# Sheet_1.net
KiCad netlist of a schematic drawn in EasyEDA
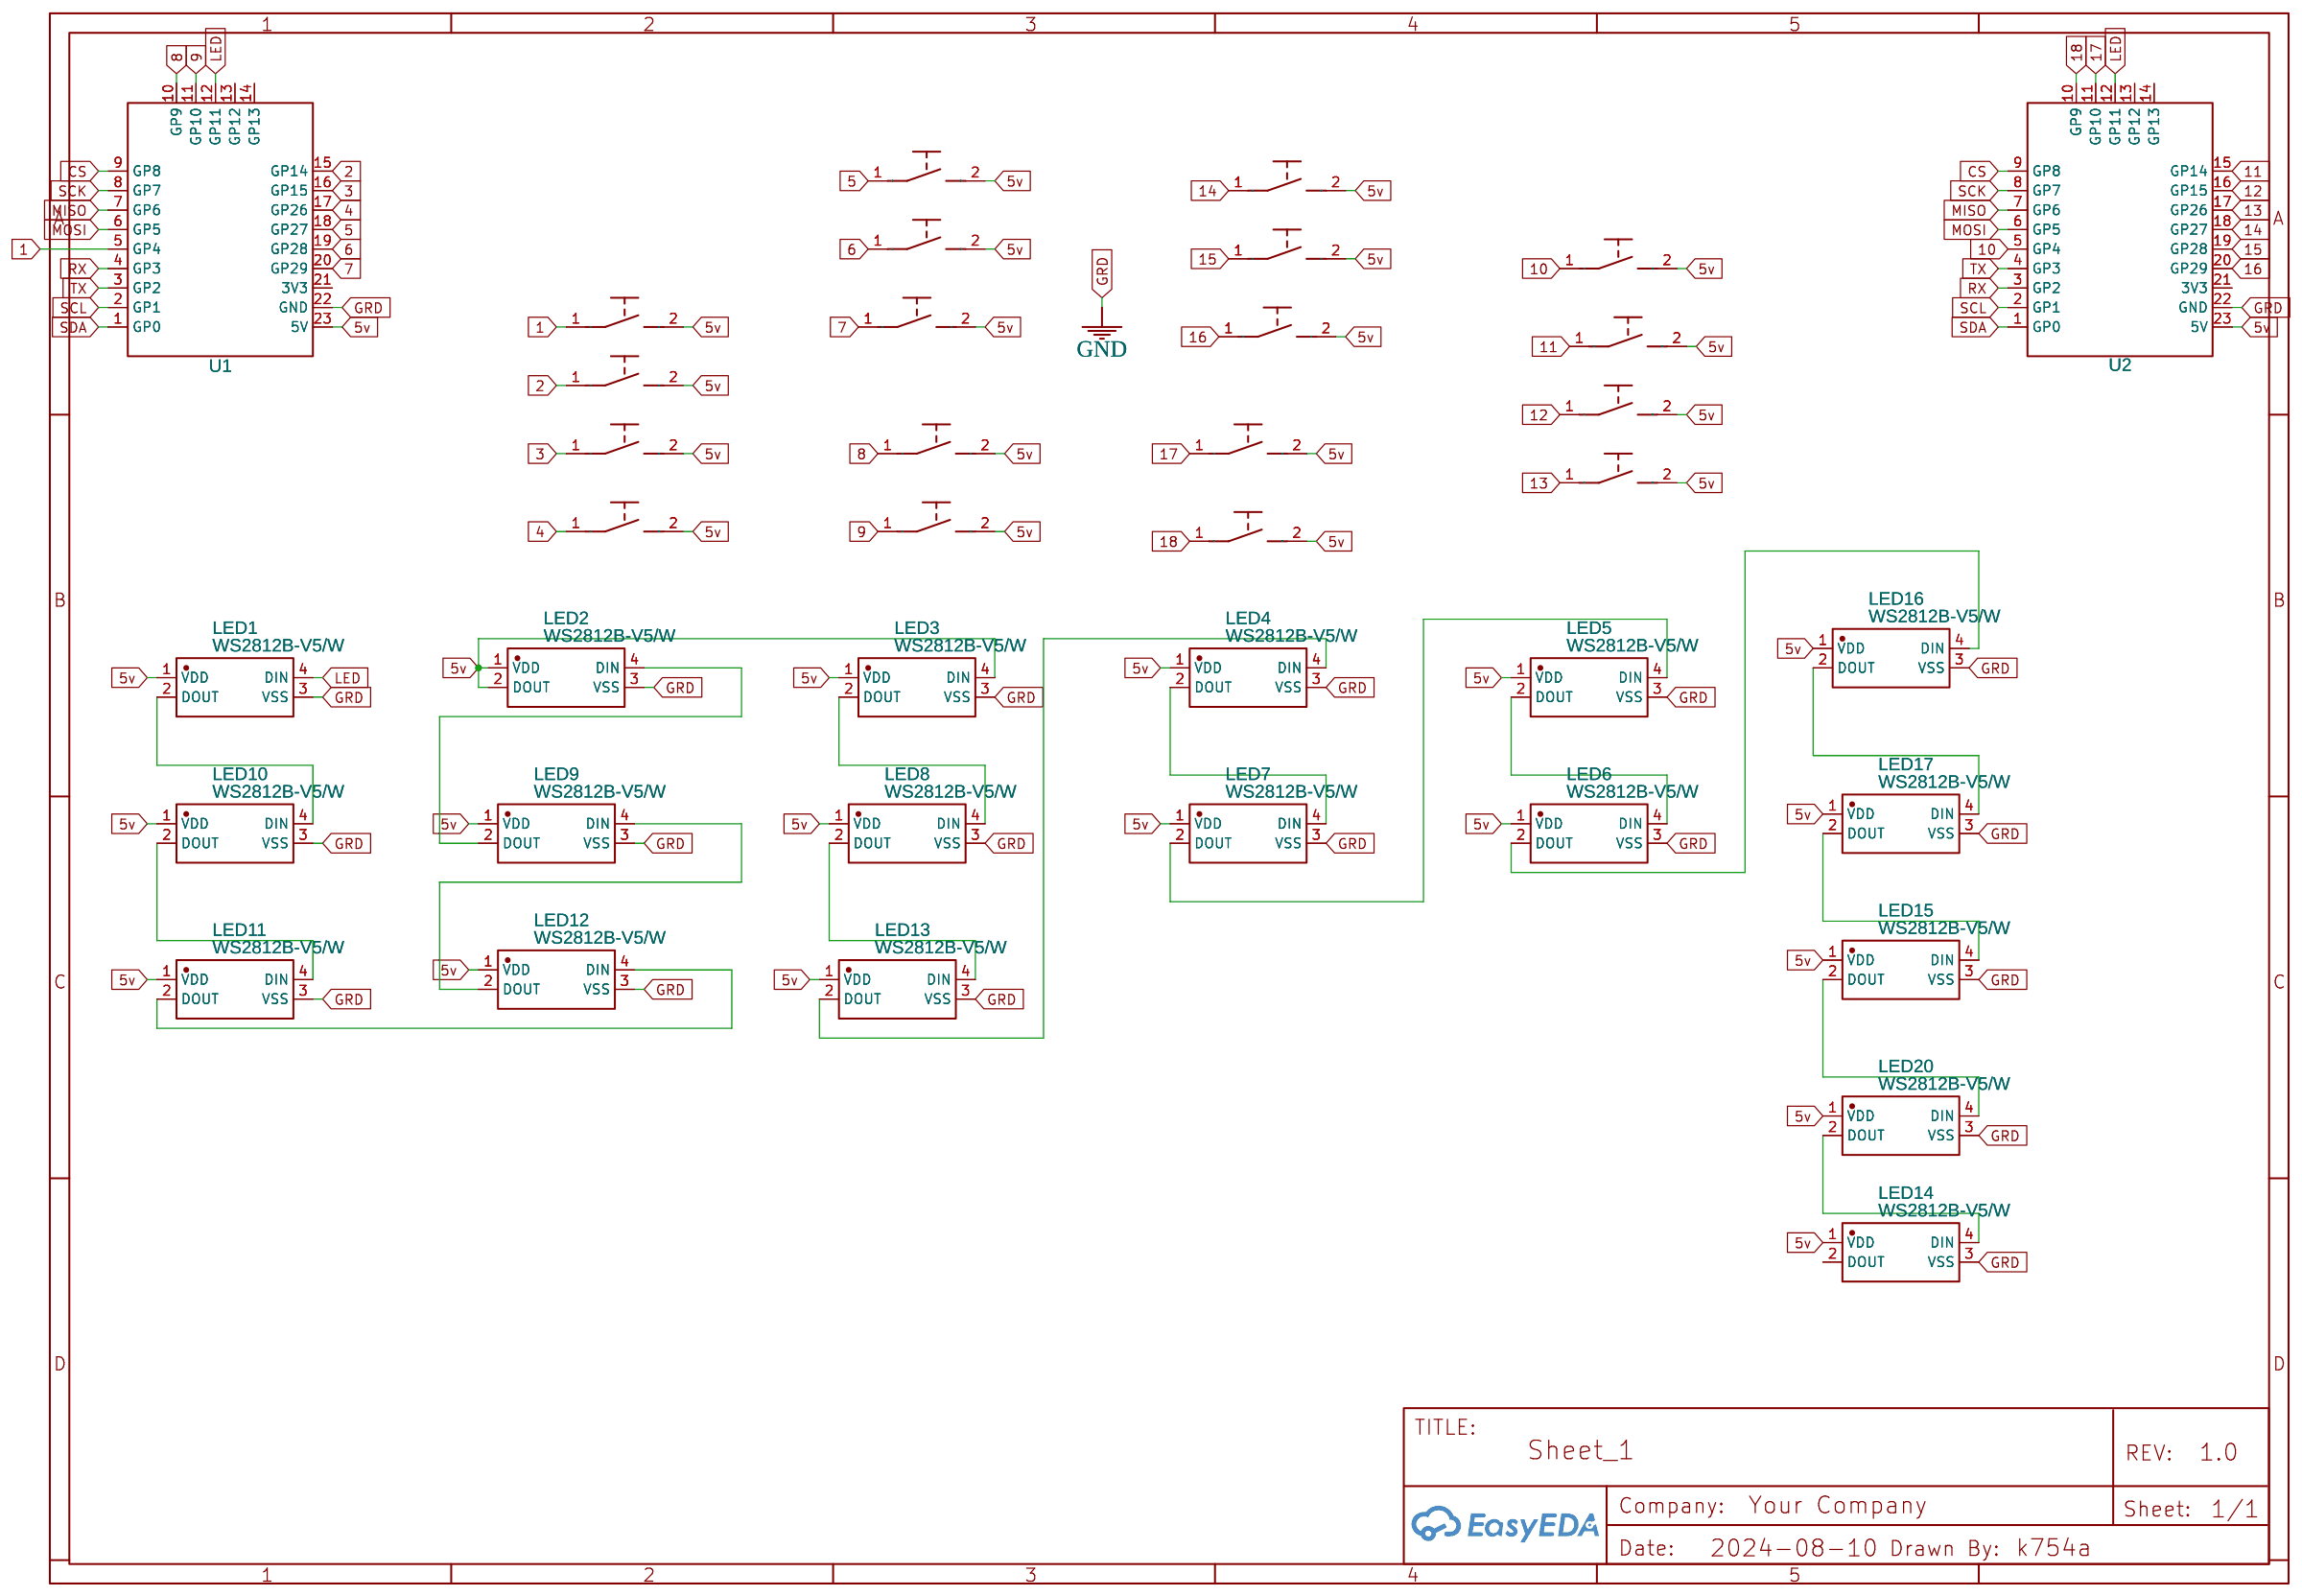
[diagram p0: schematic sheet]

(export (version "E")
  (design (tool "Eeschema 10.0.6"))
  (components
    (comp (ref "LED1")
      (value "WS2812B-V5/W")
      (fields (field (name "Manufacturer") "worldsemi"))
      (libsource (lib "") (part "WS2812B-V5/W"))
    )
    (comp (ref "LED2")
      (value "WS2812B-V5/W")
      (fields (field (name "Manufacturer") "worldsemi"))
      (libsource (lib "") (part "WS2812B-V5/W"))
    )
    (comp (ref "LED3")
      (value "WS2812B-V5/W")
      (fields (field (name "Manufacturer") "worldsemi"))
      (libsource (lib "") (part "WS2812B-V5/W"))
    )
    (comp (ref "LED4")
      (value "WS2812B-V5/W")
      (fields (field (name "Manufacturer") "worldsemi"))
      (libsource (lib "") (part "WS2812B-V5/W"))
    )
    (comp (ref "LED5")
      (value "WS2812B-V5/W")
      (fields (field (name "Manufacturer") "worldsemi"))
      (libsource (lib "") (part "WS2812B-V5/W"))
    )
    (comp (ref "LED6")
      (value "WS2812B-V5/W")
      (fields (field (name "Manufacturer") "worldsemi"))
      (libsource (lib "") (part "WS2812B-V5/W"))
    )
    (comp (ref "LED7")
      (value "WS2812B-V5/W")
      (fields (field (name "Manufacturer") "worldsemi"))
      (libsource (lib "") (part "WS2812B-V5/W"))
    )
    (comp (ref "LED8")
      (value "WS2812B-V5/W")
      (fields (field (name "Manufacturer") "worldsemi"))
      (libsource (lib "") (part "WS2812B-V5/W"))
    )
    (comp (ref "LED9")
      (value "WS2812B-V5/W")
      (fields (field (name "Manufacturer") "worldsemi"))
      (libsource (lib "") (part "WS2812B-V5/W"))
    )
    (comp (ref "LED10")
      (value "WS2812B-V5/W")
      (fields (field (name "Manufacturer") "worldsemi"))
      (libsource (lib "") (part "WS2812B-V5/W"))
    )
    (comp (ref "LED11")
      (value "WS2812B-V5/W")
      (fields (field (name "Manufacturer") "worldsemi"))
      (libsource (lib "") (part "WS2812B-V5/W"))
    )
    (comp (ref "LED12")
      (value "WS2812B-V5/W")
      (fields (field (name "Manufacturer") "worldsemi"))
      (libsource (lib "") (part "WS2812B-V5/W"))
    )
    (comp (ref "LED13")
      (value "WS2812B-V5/W")
      (fields (field (name "Manufacturer") "worldsemi"))
      (libsource (lib "") (part "WS2812B-V5/W"))
    )
    (comp (ref "LED14")
      (value "WS2812B-V5/W")
      (fields (field (name "Manufacturer") "worldsemi"))
      (libsource (lib "") (part "WS2812B-V5/W"))
    )
    (comp (ref "LED15")
      (value "WS2812B-V5/W")
      (fields (field (name "Manufacturer") "worldsemi"))
      (libsource (lib "") (part "WS2812B-V5/W"))
    )
    (comp (ref "LED16")
      (value "WS2812B-V5/W")
      (fields (field (name "Manufacturer") "worldsemi"))
      (libsource (lib "") (part "WS2812B-V5/W"))
    )
    (comp (ref "LED17")
      (value "WS2812B-V5/W")
      (fields (field (name "Manufacturer") "worldsemi"))
      (libsource (lib "") (part "WS2812B-V5/W"))
    )
    (comp (ref "LED20")
      (value "WS2812B-V5/W")
      (fields (field (name "Manufacturer") "worldsemi"))
      (libsource (lib "") (part "WS2812B-V5/W"))
    )
    (comp (ref "SW1")
      (value "CPG151101S13")
      (fields (field (name "Manufacturer") "Kailh(凯华)"))
      (libsource (lib "") (part "CPG151101S13"))
    )
    (comp (ref "SW2")
      (value "CPG151101S13")
      (fields (field (name "Manufacturer") "Kailh(凯华)"))
      (libsource (lib "") (part "CPG151101S13"))
    )
    (comp (ref "SW3")
      (value "CPG151101S13")
      (fields (field (name "Manufacturer") "Kailh(凯华)"))
      (libsource (lib "") (part "CPG151101S13"))
    )
    (comp (ref "SW4")
      (value "CPG151101S13")
      (fields (field (name "Manufacturer") "Kailh(凯华)"))
      (libsource (lib "") (part "CPG151101S13"))
    )
    (comp (ref "SW5")
      (value "CPG151101S13")
      (fields (field (name "Manufacturer") "Kailh(凯华)"))
      (libsource (lib "") (part "CPG151101S13"))
    )
    (comp (ref "SW6")
      (value "CPG151101S13")
      (fields (field (name "Manufacturer") "Kailh(凯华)"))
      (libsource (lib "") (part "CPG151101S13"))
    )
    (comp (ref "SW7")
      (value "CPG151101S13")
      (fields (field (name "Manufacturer") "Kailh(凯华)"))
      (libsource (lib "") (part "CPG151101S13"))
    )
    (comp (ref "SW8")
      (value "CPG151101S13")
      (fields (field (name "Manufacturer") "Kailh(凯华)"))
      (libsource (lib "") (part "CPG151101S13"))
    )
    (comp (ref "SW9")
      (value "CPG151101S13")
      (fields (field (name "Manufacturer") "Kailh(凯华)"))
      (libsource (lib "") (part "CPG151101S13"))
    )
    (comp (ref "SW10")
      (value "CPG151101S13")
      (fields (field (name "Manufacturer") "Kailh(凯华)"))
      (libsource (lib "") (part "CPG151101S13"))
    )
    (comp (ref "SW11")
      (value "CPG151101S13")
      (fields (field (name "Manufacturer") "Kailh(凯华)"))
      (libsource (lib "") (part "CPG151101S13"))
    )
    (comp (ref "SW12")
      (value "CPG151101S13")
      (fields (field (name "Manufacturer") "Kailh(凯华)"))
      (libsource (lib "") (part "CPG151101S13"))
    )
    (comp (ref "SW13")
      (value "CPG151101S13")
      (fields (field (name "Manufacturer") "Kailh(凯华)"))
      (libsource (lib "") (part "CPG151101S13"))
    )
    (comp (ref "SW14")
      (value "CPG151101S13")
      (fields (field (name "Manufacturer") "Kailh(凯华)"))
      (libsource (lib "") (part "CPG151101S13"))
    )
    (comp (ref "SW15")
      (value "CPG151101S13")
      (fields (field (name "Manufacturer") "Kailh(凯华)"))
      (libsource (lib "") (part "CPG151101S13"))
    )
    (comp (ref "SW16")
      (value "CPG151101S13")
      (fields (field (name "Manufacturer") "Kailh(凯华)"))
      (libsource (lib "") (part "CPG151101S13"))
    )
    (comp (ref "SW17")
      (value "CPG151101S13")
      (fields (field (name "Manufacturer") "Kailh(凯华)"))
      (libsource (lib "") (part "CPG151101S13"))
    )
    (comp (ref "SW18")
      (value "CPG151101S13")
      (fields (field (name "Manufacturer") "Kailh(凯华)"))
      (libsource (lib "") (part "CPG151101S13"))
    )
    (comp (ref "U1")
      (value "RP2040-ZERO")
      (fields
        (field (name "Manufacturer Part") "RP2040-Zero")
        (field (name "Manufacturer") "Waveshare(微雪电子)")
      )
      (libsource (lib "") (part "RP2040-ZERO"))
    )
    (comp (ref "U2")
      (value "RP2040-ZERO")
      (fields
        (field (name "Manufacturer Part") "RP2040-Zero")
        (field (name "Manufacturer") "Waveshare(微雪电子)")
      )
      (libsource (lib "") (part "RP2040-ZERO"))
    )
  )
  (nets
    (net (code "1") (name "1") (class "Default")
      (node (ref "SW1") (pin "1") (pinfunction "1_1") (pintype "unspecified"))
      (node (ref "U1") (pin "5") (pinfunction "GP4_5") (pintype "unspecified"))
    )
    (net (code "2") (name "2") (class "Default")
      (node (ref "SW2") (pin "1") (pinfunction "1_1") (pintype "unspecified"))
      (node (ref "U1") (pin "15") (pinfunction "GP14_15") (pintype "unspecified"))
    )
    (net (code "3") (name "3") (class "Default")
      (node (ref "SW3") (pin "1") (pinfunction "1_1") (pintype "unspecified"))
      (node (ref "U1") (pin "16") (pinfunction "GP15_16") (pintype "unspecified"))
    )
    (net (code "4") (name "4") (class "Default")
      (node (ref "SW4") (pin "1") (pinfunction "1_1") (pintype "unspecified"))
      (node (ref "U1") (pin "17") (pinfunction "GP26_17") (pintype "unspecified"))
    )
    (net (code "5") (name "5") (class "Default")
      (node (ref "SW5") (pin "1") (pinfunction "1_1") (pintype "unspecified"))
      (node (ref "U1") (pin "18") (pinfunction "GP27_18") (pintype "unspecified"))
    )
    (net (code "6") (name "5v") (class "Default")
      (node (ref "LED1") (pin "1") (pinfunction "VDD_1") (pintype "unspecified"))
      (node (ref "LED10") (pin "1") (pinfunction "VDD_1") (pintype "unspecified"))
      (node (ref "LED11") (pin "1") (pinfunction "VDD_1") (pintype "unspecified"))
      (node (ref "LED12") (pin "1") (pinfunction "VDD_1") (pintype "unspecified"))
      (node (ref "LED13") (pin "1") (pinfunction "VDD_1") (pintype "unspecified"))
      (node (ref "LED14") (pin "1") (pinfunction "VDD_1") (pintype "unspecified"))
      (node (ref "LED15") (pin "1") (pinfunction "VDD_1") (pintype "unspecified"))
      (node (ref "LED16") (pin "1") (pinfunction "VDD_1") (pintype "unspecified"))
      (node (ref "LED17") (pin "1") (pinfunction "VDD_1") (pintype "unspecified"))
      (node (ref "LED2") (pin "1") (pinfunction "VDD_1") (pintype "unspecified"))
      (node (ref "LED2") (pin "2") (pinfunction "DOUT_2") (pintype "unspecified"))
      (node (ref "LED20") (pin "1") (pinfunction "VDD_1") (pintype "unspecified"))
      (node (ref "LED3") (pin "1") (pinfunction "VDD_1") (pintype "unspecified"))
      (node (ref "LED3") (pin "4") (pinfunction "DIN_4") (pintype "unspecified"))
      (node (ref "LED4") (pin "1") (pinfunction "VDD_1") (pintype "unspecified"))
      (node (ref "LED5") (pin "1") (pinfunction "VDD_1") (pintype "unspecified"))
      (node (ref "LED6") (pin "1") (pinfunction "VDD_1") (pintype "unspecified"))
      (node (ref "LED7") (pin "1") (pinfunction "VDD_1") (pintype "unspecified"))
      (node (ref "LED8") (pin "1") (pinfunction "VDD_1") (pintype "unspecified"))
      (node (ref "LED9") (pin "1") (pinfunction "VDD_1") (pintype "unspecified"))
      (node (ref "SW1") (pin "2") (pinfunction "2_2") (pintype "unspecified"))
      (node (ref "SW10") (pin "2") (pinfunction "2_2") (pintype "unspecified"))
      (node (ref "SW11") (pin "2") (pinfunction "2_2") (pintype "unspecified"))
      (node (ref "SW12") (pin "2") (pinfunction "2_2") (pintype "unspecified"))
      (node (ref "SW13") (pin "2") (pinfunction "2_2") (pintype "unspecified"))
      (node (ref "SW14") (pin "2") (pinfunction "2_2") (pintype "unspecified"))
      (node (ref "SW15") (pin "2") (pinfunction "2_2") (pintype "unspecified"))
      (node (ref "SW16") (pin "2") (pinfunction "2_2") (pintype "unspecified"))
      (node (ref "SW17") (pin "2") (pinfunction "2_2") (pintype "unspecified"))
      (node (ref "SW18") (pin "2") (pinfunction "2_2") (pintype "unspecified"))
      (node (ref "SW2") (pin "2") (pinfunction "2_2") (pintype "unspecified"))
      (node (ref "SW3") (pin "2") (pinfunction "2_2") (pintype "unspecified"))
      (node (ref "SW4") (pin "2") (pinfunction "2_2") (pintype "unspecified"))
      (node (ref "SW5") (pin "2") (pinfunction "2_2") (pintype "unspecified"))
      (node (ref "SW6") (pin "2") (pinfunction "2_2") (pintype "unspecified"))
      (node (ref "SW7") (pin "2") (pinfunction "2_2") (pintype "unspecified"))
      (node (ref "SW8") (pin "2") (pinfunction "2_2") (pintype "unspecified"))
      (node (ref "SW9") (pin "2") (pinfunction "2_2") (pintype "unspecified"))
      (node (ref "U1") (pin "23") (pinfunction "5V_23") (pintype "unspecified"))
      (node (ref "U2") (pin "23") (pinfunction "5V_23") (pintype "unspecified"))
    )
    (net (code "7") (name "6") (class "Default")
      (node (ref "SW6") (pin "1") (pinfunction "1_1") (pintype "unspecified"))
      (node (ref "U1") (pin "19") (pinfunction "GP28_19") (pintype "unspecified"))
    )
    (net (code "8") (name "7") (class "Default")
      (node (ref "SW7") (pin "1") (pinfunction "1_1") (pintype "unspecified"))
      (node (ref "U1") (pin "20") (pinfunction "GP29_20") (pintype "unspecified"))
    )
    (net (code "9") (name "8") (class "Default")
      (node (ref "SW8") (pin "1") (pinfunction "1_1") (pintype "unspecified"))
      (node (ref "U1") (pin "10") (pinfunction "GP9_10") (pintype "unspecified"))
    )
    (net (code "10") (name "9") (class "Default")
      (node (ref "SW9") (pin "1") (pinfunction "1_1") (pintype "unspecified"))
      (node (ref "U1") (pin "11") (pinfunction "GP10_11") (pintype "unspecified"))
    )
    (net (code "11") (name "10") (class "Default")
      (node (ref "SW18") (pin "1") (pinfunction "1_1") (pintype "unspecified"))
      (node (ref "U2") (pin "5") (pinfunction "GP4_5") (pintype "unspecified"))
    )
    (net (code "12") (name "11") (class "Default")
      (node (ref "SW17") (pin "1") (pinfunction "1_1") (pintype "unspecified"))
      (node (ref "U2") (pin "15") (pinfunction "GP14_15") (pintype "unspecified"))
    )
    (net (code "13") (name "12") (class "Default")
      (node (ref "SW16") (pin "1") (pinfunction "1_1") (pintype "unspecified"))
      (node (ref "U2") (pin "16") (pinfunction "GP15_16") (pintype "unspecified"))
    )
    (net (code "14") (name "13") (class "Default")
      (node (ref "SW10") (pin "1") (pinfunction "1_1") (pintype "unspecified"))
      (node (ref "U2") (pin "17") (pinfunction "GP26_17") (pintype "unspecified"))
    )
    (net (code "15") (name "14") (class "Default")
      (node (ref "SW14") (pin "1") (pinfunction "1_1") (pintype "unspecified"))
      (node (ref "U2") (pin "18") (pinfunction "GP27_18") (pintype "unspecified"))
    )
    (net (code "16") (name "15") (class "Default")
      (node (ref "SW13") (pin "1") (pinfunction "1_1") (pintype "unspecified"))
      (node (ref "U2") (pin "19") (pinfunction "GP28_19") (pintype "unspecified"))
    )
    (net (code "17") (name "16") (class "Default")
      (node (ref "SW12") (pin "1") (pinfunction "1_1") (pintype "unspecified"))
      (node (ref "U2") (pin "20") (pinfunction "GP29_20") (pintype "unspecified"))
    )
    (net (code "18") (name "17") (class "Default")
      (node (ref "SW11") (pin "1") (pinfunction "1_1") (pintype "unspecified"))
      (node (ref "U2") (pin "11") (pinfunction "GP10_11") (pintype "unspecified"))
    )
    (net (code "19") (name "18") (class "Default")
      (node (ref "SW15") (pin "1") (pinfunction "1_1") (pintype "unspecified"))
      (node (ref "U2") (pin "10") (pinfunction "GP9_10") (pintype "unspecified"))
    )
    (net (code "20") (name "CS") (class "Default")
      (node (ref "U1") (pin "9") (pinfunction "GP8_9") (pintype "unspecified"))
      (node (ref "U2") (pin "9") (pinfunction "GP8_9") (pintype "unspecified"))
    )
    (net (code "21") (name "GRD") (class "Default")
      (node (ref "LED1") (pin "3") (pinfunction "VSS_3") (pintype "unspecified"))
      (node (ref "LED10") (pin "3") (pinfunction "VSS_3") (pintype "unspecified"))
      (node (ref "LED11") (pin "3") (pinfunction "VSS_3") (pintype "unspecified"))
      (node (ref "LED12") (pin "3") (pinfunction "VSS_3") (pintype "unspecified"))
      (node (ref "LED13") (pin "3") (pinfunction "VSS_3") (pintype "unspecified"))
      (node (ref "LED14") (pin "3") (pinfunction "VSS_3") (pintype "unspecified"))
      (node (ref "LED15") (pin "3") (pinfunction "VSS_3") (pintype "unspecified"))
      (node (ref "LED16") (pin "3") (pinfunction "VSS_3") (pintype "unspecified"))
      (node (ref "LED17") (pin "3") (pinfunction "VSS_3") (pintype "unspecified"))
      (node (ref "LED2") (pin "3") (pinfunction "VSS_3") (pintype "unspecified"))
      (node (ref "LED20") (pin "3") (pinfunction "VSS_3") (pintype "unspecified"))
      (node (ref "LED3") (pin "3") (pinfunction "VSS_3") (pintype "unspecified"))
      (node (ref "LED4") (pin "3") (pinfunction "VSS_3") (pintype "unspecified"))
      (node (ref "LED5") (pin "3") (pinfunction "VSS_3") (pintype "unspecified"))
      (node (ref "LED6") (pin "3") (pinfunction "VSS_3") (pintype "unspecified"))
      (node (ref "LED7") (pin "3") (pinfunction "VSS_3") (pintype "unspecified"))
      (node (ref "LED8") (pin "3") (pinfunction "VSS_3") (pintype "unspecified"))
      (node (ref "LED9") (pin "3") (pinfunction "VSS_3") (pintype "unspecified"))
      (node (ref "U1") (pin "22") (pinfunction "GND_22") (pintype "unspecified"))
      (node (ref "U2") (pin "22") (pinfunction "GND_22") (pintype "unspecified"))
    )
    (net (code "22") (name "LED") (class "Default")
      (node (ref "LED1") (pin "4") (pinfunction "DIN_4") (pintype "unspecified"))
      (node (ref "U1") (pin "12") (pinfunction "GP11_12") (pintype "unspecified"))
      (node (ref "U2") (pin "12") (pinfunction "GP11_12") (pintype "unspecified"))
    )
    (net (code "23") (name "MISO") (class "Default")
      (node (ref "U1") (pin "7") (pinfunction "GP6_7") (pintype "unspecified"))
      (node (ref "U2") (pin "7") (pinfunction "GP6_7") (pintype "unspecified"))
    )
    (net (code "24") (name "MOSI") (class "Default")
      (node (ref "U1") (pin "6") (pinfunction "GP5_6") (pintype "unspecified"))
      (node (ref "U2") (pin "6") (pinfunction "GP5_6") (pintype "unspecified"))
    )
    (net (code "25") (name "Net-(LED1-DOUT)") (class "Default")
      (node (ref "LED1") (pin "2") (pinfunction "DOUT_2") (pintype "unspecified"))
      (node (ref "LED10") (pin "4") (pinfunction "DIN_4") (pintype "unspecified"))
    )
    (net (code "26") (name "Net-(LED2-DIN)") (class "Default")
      (node (ref "LED2") (pin "4") (pinfunction "DIN_4") (pintype "unspecified"))
      (node (ref "LED9") (pin "2") (pinfunction "DOUT_2") (pintype "unspecified"))
    )
    (net (code "27") (name "Net-(LED3-DOUT)") (class "Default")
      (node (ref "LED3") (pin "2") (pinfunction "DOUT_2") (pintype "unspecified"))
      (node (ref "LED8") (pin "4") (pinfunction "DIN_4") (pintype "unspecified"))
    )
    (net (code "28") (name "Net-(LED4-DOUT)") (class "Default")
      (node (ref "LED4") (pin "2") (pinfunction "DOUT_2") (pintype "unspecified"))
      (node (ref "LED7") (pin "4") (pinfunction "DIN_4") (pintype "unspecified"))
    )
    (net (code "29") (name "Net-(LED5-DIN)") (class "Default")
      (node (ref "LED5") (pin "4") (pinfunction "DIN_4") (pintype "unspecified"))
      (node (ref "LED7") (pin "2") (pinfunction "DOUT_2") (pintype "unspecified"))
    )
    (net (code "30") (name "Net-(LED5-DOUT)") (class "Default")
      (node (ref "LED5") (pin "2") (pinfunction "DOUT_2") (pintype "unspecified"))
      (node (ref "LED6") (pin "4") (pinfunction "DIN_4") (pintype "unspecified"))
    )
    (net (code "31") (name "Net-(LED10-DOUT)") (class "Default")
      (node (ref "LED10") (pin "2") (pinfunction "DOUT_2") (pintype "unspecified"))
      (node (ref "LED11") (pin "4") (pinfunction "DIN_4") (pintype "unspecified"))
    )
    (net (code "32") (name "Net-(LED11-DOUT)") (class "Default")
      (node (ref "LED11") (pin "2") (pinfunction "DOUT_2") (pintype "unspecified"))
      (node (ref "LED12") (pin "4") (pinfunction "DIN_4") (pintype "unspecified"))
    )
    (net (code "33") (name "Net-(LED12-DOUT)") (class "Default")
      (node (ref "LED12") (pin "2") (pinfunction "DOUT_2") (pintype "unspecified"))
      (node (ref "LED9") (pin "4") (pinfunction "DIN_4") (pintype "unspecified"))
    )
    (net (code "34") (name "Net-(LED13-DIN)") (class "Default")
      (node (ref "LED13") (pin "4") (pinfunction "DIN_4") (pintype "unspecified"))
      (node (ref "LED8") (pin "2") (pinfunction "DOUT_2") (pintype "unspecified"))
    )
    (net (code "35") (name "Net-(LED13-DOUT)") (class "Default")
      (node (ref "LED13") (pin "2") (pinfunction "DOUT_2") (pintype "unspecified"))
      (node (ref "LED4") (pin "4") (pinfunction "DIN_4") (pintype "unspecified"))
    )
    (net (code "36") (name "Net-(LED14-DIN)") (class "Default")
      (node (ref "LED14") (pin "4") (pinfunction "DIN_4") (pintype "unspecified"))
      (node (ref "LED20") (pin "2") (pinfunction "DOUT_2") (pintype "unspecified"))
    )
    (net (code "37") (name "Net-(LED15-DIN)") (class "Default")
      (node (ref "LED15") (pin "4") (pinfunction "DIN_4") (pintype "unspecified"))
      (node (ref "LED17") (pin "2") (pinfunction "DOUT_2") (pintype "unspecified"))
    )
    (net (code "38") (name "Net-(LED15-DOUT)") (class "Default")
      (node (ref "LED15") (pin "2") (pinfunction "DOUT_2") (pintype "unspecified"))
      (node (ref "LED20") (pin "4") (pinfunction "DIN_4") (pintype "unspecified"))
    )
    (net (code "39") (name "Net-(LED16-DIN)") (class "Default")
      (node (ref "LED16") (pin "4") (pinfunction "DIN_4") (pintype "unspecified"))
      (node (ref "LED6") (pin "2") (pinfunction "DOUT_2") (pintype "unspecified"))
    )
    (net (code "40") (name "Net-(LED16-DOUT)") (class "Default")
      (node (ref "LED16") (pin "2") (pinfunction "DOUT_2") (pintype "unspecified"))
      (node (ref "LED17") (pin "4") (pinfunction "DIN_4") (pintype "unspecified"))
    )
    (net (code "41") (name "RX") (class "Default")
      (node (ref "U1") (pin "4") (pinfunction "GP3_4") (pintype "unspecified"))
      (node (ref "U2") (pin "3") (pinfunction "GP2_3") (pintype "unspecified"))
    )
    (net (code "42") (name "SCK") (class "Default")
      (node (ref "U1") (pin "8") (pinfunction "GP7_8") (pintype "unspecified"))
      (node (ref "U2") (pin "8") (pinfunction "GP7_8") (pintype "unspecified"))
    )
    (net (code "43") (name "SCL") (class "Default")
      (node (ref "U1") (pin "2") (pinfunction "GP1_2") (pintype "unspecified"))
      (node (ref "U2") (pin "2") (pinfunction "GP1_2") (pintype "unspecified"))
    )
    (net (code "44") (name "SDA") (class "Default")
      (node (ref "U1") (pin "1") (pinfunction "GP0_1") (pintype "unspecified"))
      (node (ref "U2") (pin "1") (pinfunction "GP0_1") (pintype "unspecified"))
    )
    (net (code "45") (name "TX") (class "Default")
      (node (ref "U1") (pin "3") (pinfunction "GP2_3") (pintype "unspecified"))
      (node (ref "U2") (pin "4") (pinfunction "GP3_4") (pintype "unspecified"))
    )
    (net (code "46") (name "unconnected-(LED14-DOUT-Pad2)") (class "Default")
      (node (ref "LED14") (pin "2") (pinfunction "DOUT_2") (pintype "unspecified"))
    )
    (net (code "47") (name "unconnected-(U1-3V3-Pad21)") (class "Default")
      (node (ref "U1") (pin "21") (pinfunction "3V3_21") (pintype "unspecified"))
    )
    (net (code "48") (name "unconnected-(U1-GP12-Pad13)") (class "Default")
      (node (ref "U1") (pin "13") (pinfunction "GP12_13") (pintype "unspecified"))
    )
    (net (code "49") (name "unconnected-(U1-GP13-Pad14)") (class "Default")
      (node (ref "U1") (pin "14") (pinfunction "GP13_14") (pintype "unspecified"))
    )
    (net (code "50") (name "unconnected-(U2-3V3-Pad21)") (class "Default")
      (node (ref "U2") (pin "21") (pinfunction "3V3_21") (pintype "unspecified"))
    )
    (net (code "51") (name "unconnected-(U2-GP12-Pad13)") (class "Default")
      (node (ref "U2") (pin "13") (pinfunction "GP12_13") (pintype "unspecified"))
    )
    (net (code "52") (name "unconnected-(U2-GP13-Pad14)") (class "Default")
      (node (ref "U2") (pin "14") (pinfunction "GP13_14") (pintype "unspecified"))
    )
  )
)
